# final_3_stages.net
KiCad netlist of a schematic drawn in EAGLE
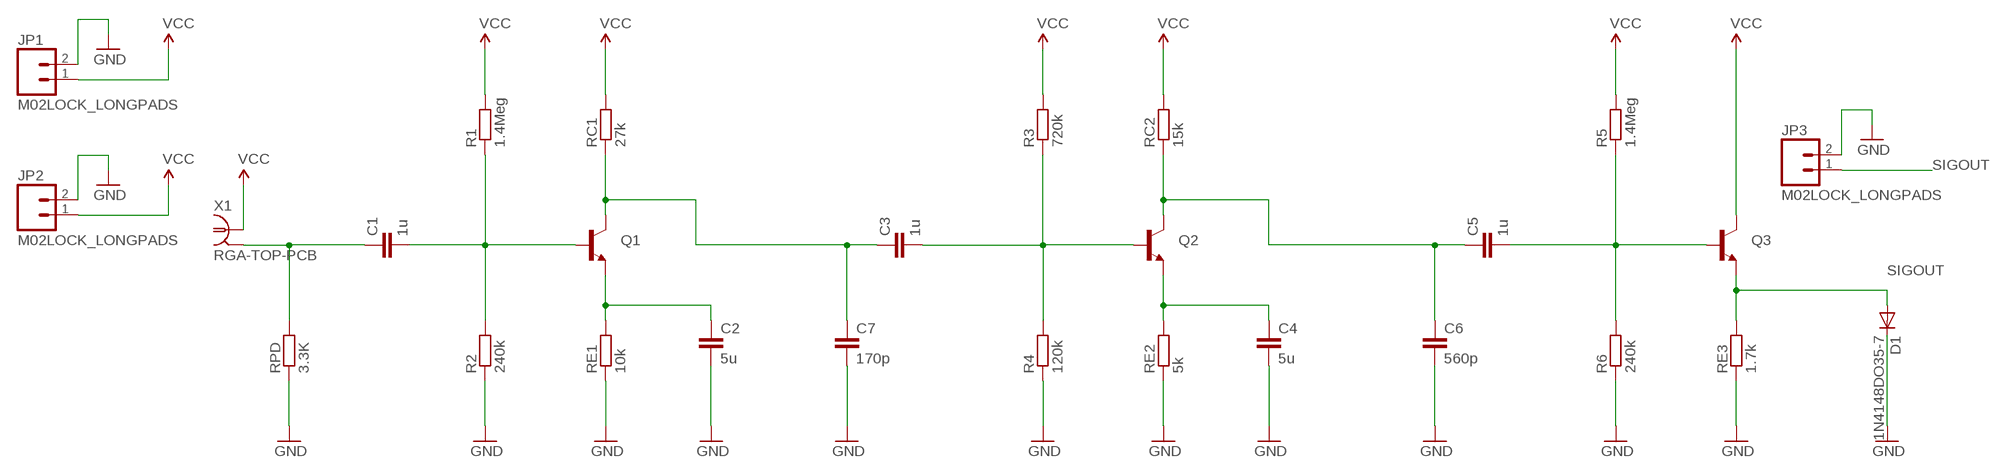
[diagram p0: schematic, sheet 1]

(export (version "E")
  (design (tool "Eeschema 10.0.6"))
  (components
    (comp (ref "C1")
      (value "1u")
      (footprint "eagle-import:CAP-PTH-SMALL-KIT")
      (libsource (lib "eagle-import") (part "CAPKIT"))
    )
    (comp (ref "C2")
      (value "5u")
      (footprint "eagle-import:CAP-PTH-SMALL-KIT")
      (libsource (lib "eagle-import") (part "CAPKIT"))
    )
    (comp (ref "C3")
      (value "1u")
      (footprint "eagle-import:CAP-PTH-SMALL-KIT")
      (libsource (lib "eagle-import") (part "CAPKIT"))
    )
    (comp (ref "C4")
      (value "5u")
      (footprint "eagle-import:CAP-PTH-SMALL-KIT")
      (libsource (lib "eagle-import") (part "CAPKIT"))
    )
    (comp (ref "C5")
      (value "1u")
      (footprint "eagle-import:CAP-PTH-SMALL-KIT")
      (libsource (lib "eagle-import") (part "CAPKIT"))
    )
    (comp (ref "C6")
      (value "560p")
      (footprint "eagle-import:CAP-PTH-SMALL-KIT")
      (libsource (lib "eagle-import") (part "CAPKIT"))
    )
    (comp (ref "C7")
      (value "170p")
      (footprint "eagle-import:CAP-PTH-SMALL-KIT")
      (libsource (lib "eagle-import") (part "CAPKIT"))
    )
    (comp (ref "D1")
      (value "1N4148DO35-7")
      (footprint "eagle-import:DO35-7")
      (libsource (lib "eagle-import") (part "1N4148DO35-7"))
    )
    (comp (ref "JP1")
      (value "M02LOCK_LONGPADS")
      (footprint "eagle-import:1X02_LOCK_LONGPADS")
      (libsource (lib "eagle-import") (part "M02LOCK_LONGPADS"))
    )
    (comp (ref "JP2")
      (value "M02LOCK_LONGPADS")
      (footprint "eagle-import:1X02_LOCK_LONGPADS")
      (libsource (lib "eagle-import") (part "M02LOCK_LONGPADS"))
    )
    (comp (ref "JP3")
      (value "M02LOCK_LONGPADS")
      (footprint "eagle-import:1X02_LOCK_LONGPADS")
      (libsource (lib "eagle-import") (part "M02LOCK_LONGPADS"))
    )
    (comp (ref "Q1")
      (value "TRANSISTOR_NPN2N3904")
      (footprint "eagle-import:TO-92")
      (libsource (lib "eagle-import") (part "TRANSISTOR_NPN2N3904"))
    )
    (comp (ref "Q2")
      (value "TRANSISTOR_NPN2N3904")
      (footprint "eagle-import:TO-92")
      (libsource (lib "eagle-import") (part "TRANSISTOR_NPN2N3904"))
    )
    (comp (ref "Q3")
      (value "TRANSISTOR_NPN2N3904")
      (footprint "eagle-import:TO-92")
      (libsource (lib "eagle-import") (part "TRANSISTOR_NPN2N3904"))
    )
    (comp (ref "R1")
      (value "1.4Meg")
      (footprint "eagle-import:0207_10")
      (libsource (lib "eagle-import") (part "R0207/10"))
    )
    (comp (ref "R2")
      (value "240k")
      (footprint "eagle-import:0207_10")
      (libsource (lib "eagle-import") (part "R0207/10"))
    )
    (comp (ref "R3")
      (value "720k")
      (footprint "eagle-import:0207_10")
      (libsource (lib "eagle-import") (part "R0207/10"))
    )
    (comp (ref "R4")
      (value "120k")
      (footprint "eagle-import:0207_10")
      (libsource (lib "eagle-import") (part "R0207/10"))
    )
    (comp (ref "R5")
      (value "1.4Meg")
      (footprint "eagle-import:0207_10")
      (libsource (lib "eagle-import") (part "R0207/10"))
    )
    (comp (ref "R6")
      (value "240k")
      (footprint "eagle-import:0207_10")
      (libsource (lib "eagle-import") (part "R0207/10"))
    )
    (comp (ref "RC1")
      (value "27k")
      (footprint "eagle-import:0207_10")
      (libsource (lib "eagle-import") (part "R0207/10"))
    )
    (comp (ref "RC2")
      (value "15k")
      (footprint "eagle-import:0207_10")
      (libsource (lib "eagle-import") (part "R0207/10"))
    )
    (comp (ref "RE1")
      (value "10k")
      (footprint "eagle-import:0207_10")
      (libsource (lib "eagle-import") (part "R0207/10"))
    )
    (comp (ref "RE2")
      (value "5k")
      (footprint "eagle-import:0207_10")
      (libsource (lib "eagle-import") (part "R0207/10"))
    )
    (comp (ref "RE3")
      (value "1.7k")
      (footprint "eagle-import:0207_10")
      (libsource (lib "eagle-import") (part "R0207/10"))
    )
    (comp (ref "RPD")
      (value "3.3K")
      (footprint "eagle-import:0207_10")
      (libsource (lib "eagle-import") (part "R0207/10"))
    )
    (comp (ref "X1")
      (value "RGA-TOP-PCB")
      (footprint "eagle-import:BNC-RGA")
      (libsource (lib "eagle-import") (part "RGA-TOP-PCB"))
    )
  )
  (nets
    (net (code "1") (name "/SIGOUT") (class "Default")
      (node (ref "D1") (pin "A") (pinfunction "A_A") (pintype "passive"))
      (node (ref "JP3") (pin "1") (pinfunction "1_1") (pintype "passive"))
      (node (ref "Q3") (pin "1") (pinfunction "E_1") (pintype "passive"))
      (node (ref "RE3") (pin "2") (pinfunction "2_2") (pintype "passive"))
    )
    (net (code "2") (name "GND") (class "Default")
      (node (ref "C2") (pin "2") (pinfunction "2_2") (pintype "passive"))
      (node (ref "C4") (pin "2") (pinfunction "2_2") (pintype "passive"))
      (node (ref "C6") (pin "2") (pinfunction "2_2") (pintype "passive"))
      (node (ref "C7") (pin "2") (pinfunction "2_2") (pintype "passive"))
      (node (ref "D1") (pin "C") (pinfunction "C_C") (pintype "passive"))
      (node (ref "JP1") (pin "2") (pinfunction "2_2") (pintype "passive"))
      (node (ref "JP2") (pin "2") (pinfunction "2_2") (pintype "passive"))
      (node (ref "JP3") (pin "2") (pinfunction "2_2") (pintype "passive"))
      (node (ref "R2") (pin "1") (pinfunction "1_1") (pintype "passive"))
      (node (ref "R4") (pin "1") (pinfunction "1_1") (pintype "passive"))
      (node (ref "R6") (pin "1") (pinfunction "1_1") (pintype "passive"))
      (node (ref "RE1") (pin "1") (pinfunction "1_1") (pintype "passive"))
      (node (ref "RE2") (pin "1") (pinfunction "1_1") (pintype "passive"))
      (node (ref "RE3") (pin "1") (pinfunction "1_1") (pintype "passive"))
      (node (ref "RPD") (pin "1") (pinfunction "1_1") (pintype "passive"))
    )
    (net (code "3") (name "Net-(C1-Pad1)") (class "Default")
      (node (ref "C1") (pin "1") (pinfunction "1_1") (pintype "passive"))
      (node (ref "RPD") (pin "2") (pinfunction "2_2") (pintype "passive"))
      (node (ref "X1") (pin "2") (pinfunction "2_2") (pintype "passive"))
      (node (ref "X1") (pin "3") (pinfunction "2_3") (pintype "passive"))
      (node (ref "X1") (pin "4") (pinfunction "2_4") (pintype "passive"))
      (node (ref "X1") (pin "5") (pinfunction "2_5") (pintype "passive"))
    )
    (net (code "4") (name "Net-(Q1-B)") (class "Default")
      (node (ref "C1") (pin "2") (pinfunction "2_2") (pintype "passive"))
      (node (ref "Q1") (pin "2") (pinfunction "B_2") (pintype "passive"))
      (node (ref "R1") (pin "1") (pinfunction "1_1") (pintype "passive"))
      (node (ref "R2") (pin "2") (pinfunction "2_2") (pintype "passive"))
    )
    (net (code "5") (name "Net-(Q1-C)") (class "Default")
      (node (ref "C3") (pin "1") (pinfunction "1_1") (pintype "passive"))
      (node (ref "C7") (pin "1") (pinfunction "1_1") (pintype "passive"))
      (node (ref "Q1") (pin "3") (pinfunction "C_3") (pintype "passive"))
      (node (ref "RC1") (pin "1") (pinfunction "1_1") (pintype "passive"))
    )
    (net (code "6") (name "Net-(Q1-E)") (class "Default")
      (node (ref "C2") (pin "1") (pinfunction "1_1") (pintype "passive"))
      (node (ref "Q1") (pin "1") (pinfunction "E_1") (pintype "passive"))
      (node (ref "RE1") (pin "2") (pinfunction "2_2") (pintype "passive"))
    )
    (net (code "7") (name "Net-(Q2-B)") (class "Default")
      (node (ref "C3") (pin "2") (pinfunction "2_2") (pintype "passive"))
      (node (ref "Q2") (pin "2") (pinfunction "B_2") (pintype "passive"))
      (node (ref "R3") (pin "1") (pinfunction "1_1") (pintype "passive"))
      (node (ref "R4") (pin "2") (pinfunction "2_2") (pintype "passive"))
    )
    (net (code "8") (name "Net-(Q2-C)") (class "Default")
      (node (ref "C5") (pin "1") (pinfunction "1_1") (pintype "passive"))
      (node (ref "C6") (pin "1") (pinfunction "1_1") (pintype "passive"))
      (node (ref "Q2") (pin "3") (pinfunction "C_3") (pintype "passive"))
      (node (ref "RC2") (pin "1") (pinfunction "1_1") (pintype "passive"))
    )
    (net (code "9") (name "Net-(Q2-E)") (class "Default")
      (node (ref "C4") (pin "1") (pinfunction "1_1") (pintype "passive"))
      (node (ref "Q2") (pin "1") (pinfunction "E_1") (pintype "passive"))
      (node (ref "RE2") (pin "2") (pinfunction "2_2") (pintype "passive"))
    )
    (net (code "10") (name "Net-(Q3-B)") (class "Default")
      (node (ref "C5") (pin "2") (pinfunction "2_2") (pintype "passive"))
      (node (ref "Q3") (pin "2") (pinfunction "B_2") (pintype "passive"))
      (node (ref "R5") (pin "1") (pinfunction "1_1") (pintype "passive"))
      (node (ref "R6") (pin "2") (pinfunction "2_2") (pintype "passive"))
    )
    (net (code "11") (name "VCC") (class "Default")
      (node (ref "JP1") (pin "1") (pinfunction "1_1") (pintype "passive"))
      (node (ref "JP2") (pin "1") (pinfunction "1_1") (pintype "passive"))
      (node (ref "Q3") (pin "3") (pinfunction "C_3") (pintype "passive"))
      (node (ref "R1") (pin "2") (pinfunction "2_2") (pintype "passive"))
      (node (ref "R3") (pin "2") (pinfunction "2_2") (pintype "passive"))
      (node (ref "R5") (pin "2") (pinfunction "2_2") (pintype "passive"))
      (node (ref "RC1") (pin "2") (pinfunction "2_2") (pintype "passive"))
      (node (ref "RC2") (pin "2") (pinfunction "2_2") (pintype "passive"))
      (node (ref "X1") (pin "1") (pinfunction "1_1") (pintype "passive"))
    )
  )
)
